# photon_IVspy.net
KiCad netlist of a schematic drawn in EAGLE
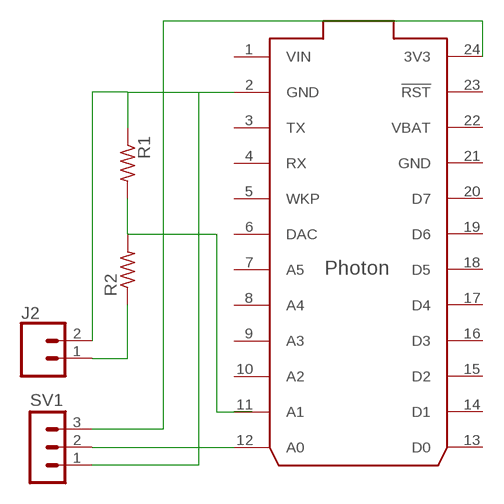
[diagram p0: schematic, sheet 1]

(export (version "E")
  (design (tool "Eeschema 10.0.6"))
  (components
    (comp (ref "J2")
      (value "CONN_023.5MM")
      (footprint "eagle-import:SCREWTERMINAL-3.5MM-2")
      (libsource (lib "eagle-import") (part "CONN_023.5MM"))
    )
    (comp (ref "R1")
      (value "R-US_0207/10")
      (footprint "eagle-import:0207_10")
      (libsource (lib "eagle-import") (part "R-US_0207/10"))
    )
    (comp (ref "R2")
      (value "R-US_0207/10")
      (footprint "eagle-import:0207_10")
      (libsource (lib "eagle-import") (part "R-US_0207/10"))
    )
    (comp (ref "SV1")
      (value "MA03-1")
      (footprint "eagle-import:MA03-1")
      (libsource (lib "eagle-import") (part "MA03-1"))
    )
    (comp (ref "U$1")
      (value "PHOTON_WITH_HEADERS")
      (footprint "eagle-import:PHOTON")
      (libsource (lib "eagle-import") (part "PHOTON_WITH_HEADERS"))
    )
  )
  (nets
    (net (code "1") (name "/GND") (class "Default")
      (node (ref "U$1") (pin "21") (pinfunction "GND_21") (pintype "power_in"))
    )
    (net (code "2") (name "/VBAT") (class "Default")
      (node (ref "U$1") (pin "22") (pinfunction "VBAT_22") (pintype "power_in"))
    )
    (net (code "3") (name "/VIN") (class "Default")
      (node (ref "U$1") (pin "1") (pinfunction "VIN_1") (pintype "power_in"))
    )
    (net (code "4") (name "Net-(J2-Pad1)") (class "Default")
      (node (ref "J2") (pin "1") (pinfunction "1_1") (pintype "passive"))
      (node (ref "R2") (pin "1") (pinfunction "1_1") (pintype "passive"))
    )
    (net (code "5") (name "Net-(J2-Pad2)") (class "Default")
      (node (ref "J2") (pin "2") (pinfunction "2_2") (pintype "passive"))
      (node (ref "R1") (pin "1") (pinfunction "1_1") (pintype "passive"))
      (node (ref "SV1") (pin "1") (pinfunction "1_1") (pintype "passive"))
      (node (ref "U$1") (pin "2") (pinfunction "GND_2") (pintype "power_in"))
    )
    (net (code "6") (name "Net-(U$1-3V3)") (class "Default")
      (node (ref "SV1") (pin "3") (pinfunction "3_3") (pintype "passive"))
      (node (ref "U$1") (pin "24") (pinfunction "3V3_24") (pintype "power_in"))
    )
    (net (code "7") (name "Net-(U$1-A0)") (class "Default")
      (node (ref "SV1") (pin "2") (pinfunction "2_2") (pintype "passive"))
      (node (ref "U$1") (pin "12") (pinfunction "A0_12") (pintype "bidirectional"))
    )
    (net (code "8") (name "Net-(U$1-A1)") (class "Default")
      (node (ref "R1") (pin "2") (pinfunction "2_2") (pintype "passive"))
      (node (ref "R2") (pin "2") (pinfunction "2_2") (pintype "passive"))
      (node (ref "U$1") (pin "11") (pinfunction "A1_11") (pintype "bidirectional"))
    )
    (net (code "9") (name "unconnected-(U$1-A2-Pad10)") (class "Default")
      (node (ref "U$1") (pin "10") (pinfunction "A2_10") (pintype "bidirectional"))
    )
    (net (code "10") (name "unconnected-(U$1-A3-Pad9)") (class "Default")
      (node (ref "U$1") (pin "9") (pinfunction "A3_9") (pintype "bidirectional"))
    )
    (net (code "11") (name "unconnected-(U$1-A4-Pad8)") (class "Default")
      (node (ref "U$1") (pin "8") (pinfunction "A4_8") (pintype "bidirectional"))
    )
    (net (code "12") (name "unconnected-(U$1-A5-Pad7)") (class "Default")
      (node (ref "U$1") (pin "7") (pinfunction "A5_7") (pintype "bidirectional"))
    )
    (net (code "13") (name "unconnected-(U$1-D0-Pad13)") (class "Default")
      (node (ref "U$1") (pin "13") (pinfunction "D0_13") (pintype "bidirectional"))
    )
    (net (code "14") (name "unconnected-(U$1-D1-Pad14)") (class "Default")
      (node (ref "U$1") (pin "14") (pinfunction "D1_14") (pintype "bidirectional"))
    )
    (net (code "15") (name "unconnected-(U$1-D2-Pad15)") (class "Default")
      (node (ref "U$1") (pin "15") (pinfunction "D2_15") (pintype "bidirectional"))
    )
    (net (code "16") (name "unconnected-(U$1-D3-Pad16)") (class "Default")
      (node (ref "U$1") (pin "16") (pinfunction "D3_16") (pintype "bidirectional"))
    )
    (net (code "17") (name "unconnected-(U$1-D4-Pad17)") (class "Default")
      (node (ref "U$1") (pin "17") (pinfunction "D4_17") (pintype "bidirectional"))
    )
    (net (code "18") (name "unconnected-(U$1-D5-Pad18)") (class "Default")
      (node (ref "U$1") (pin "18") (pinfunction "D5_18") (pintype "bidirectional"))
    )
    (net (code "19") (name "unconnected-(U$1-D6-Pad19)") (class "Default")
      (node (ref "U$1") (pin "19") (pinfunction "D6_19") (pintype "bidirectional"))
    )
    (net (code "20") (name "unconnected-(U$1-D7-Pad20)") (class "Default")
      (node (ref "U$1") (pin "20") (pinfunction "D7_20") (pintype "bidirectional"))
    )
    (net (code "21") (name "unconnected-(U$1-DAC-Pad6)") (class "Default")
      (node (ref "U$1") (pin "6") (pinfunction "DAC_6") (pintype "bidirectional"))
    )
    (net (code "22") (name "unconnected-(U$1-RX-Pad4)") (class "Default")
      (node (ref "U$1") (pin "4") (pinfunction "RX_4") (pintype "bidirectional"))
    )
    (net (code "23") (name "unconnected-(U$1-TX-Pad3)") (class "Default")
      (node (ref "U$1") (pin "3") (pinfunction "TX_3") (pintype "bidirectional"))
    )
    (net (code "24") (name "unconnected-(U$1-WKP-Pad5)") (class "Default")
      (node (ref "U$1") (pin "5") (pinfunction "WKP_5") (pintype "bidirectional"))
    )
    (net (code "25") (name "unconnected-(U$1-~{RST}-Pad23)") (class "Default")
      (node (ref "U$1") (pin "23") (pinfunction "~{RST}_23") (pintype "bidirectional"))
    )
  )
)
